# 06_interface.net
KiCad netlist of a schematic drawn in Altium Designer
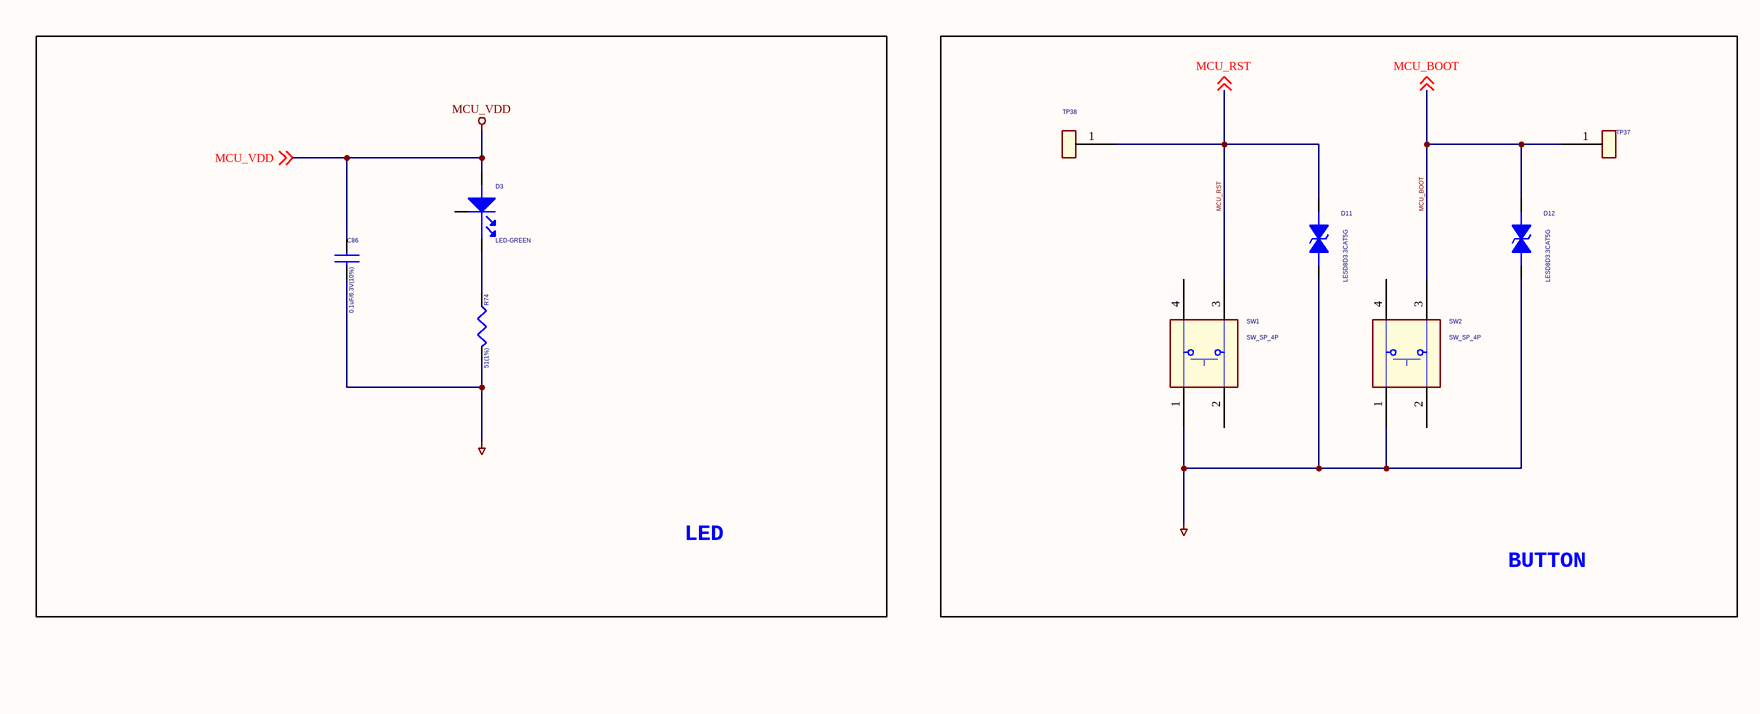
[diagram p0: 06_interface.SchDoc, left]
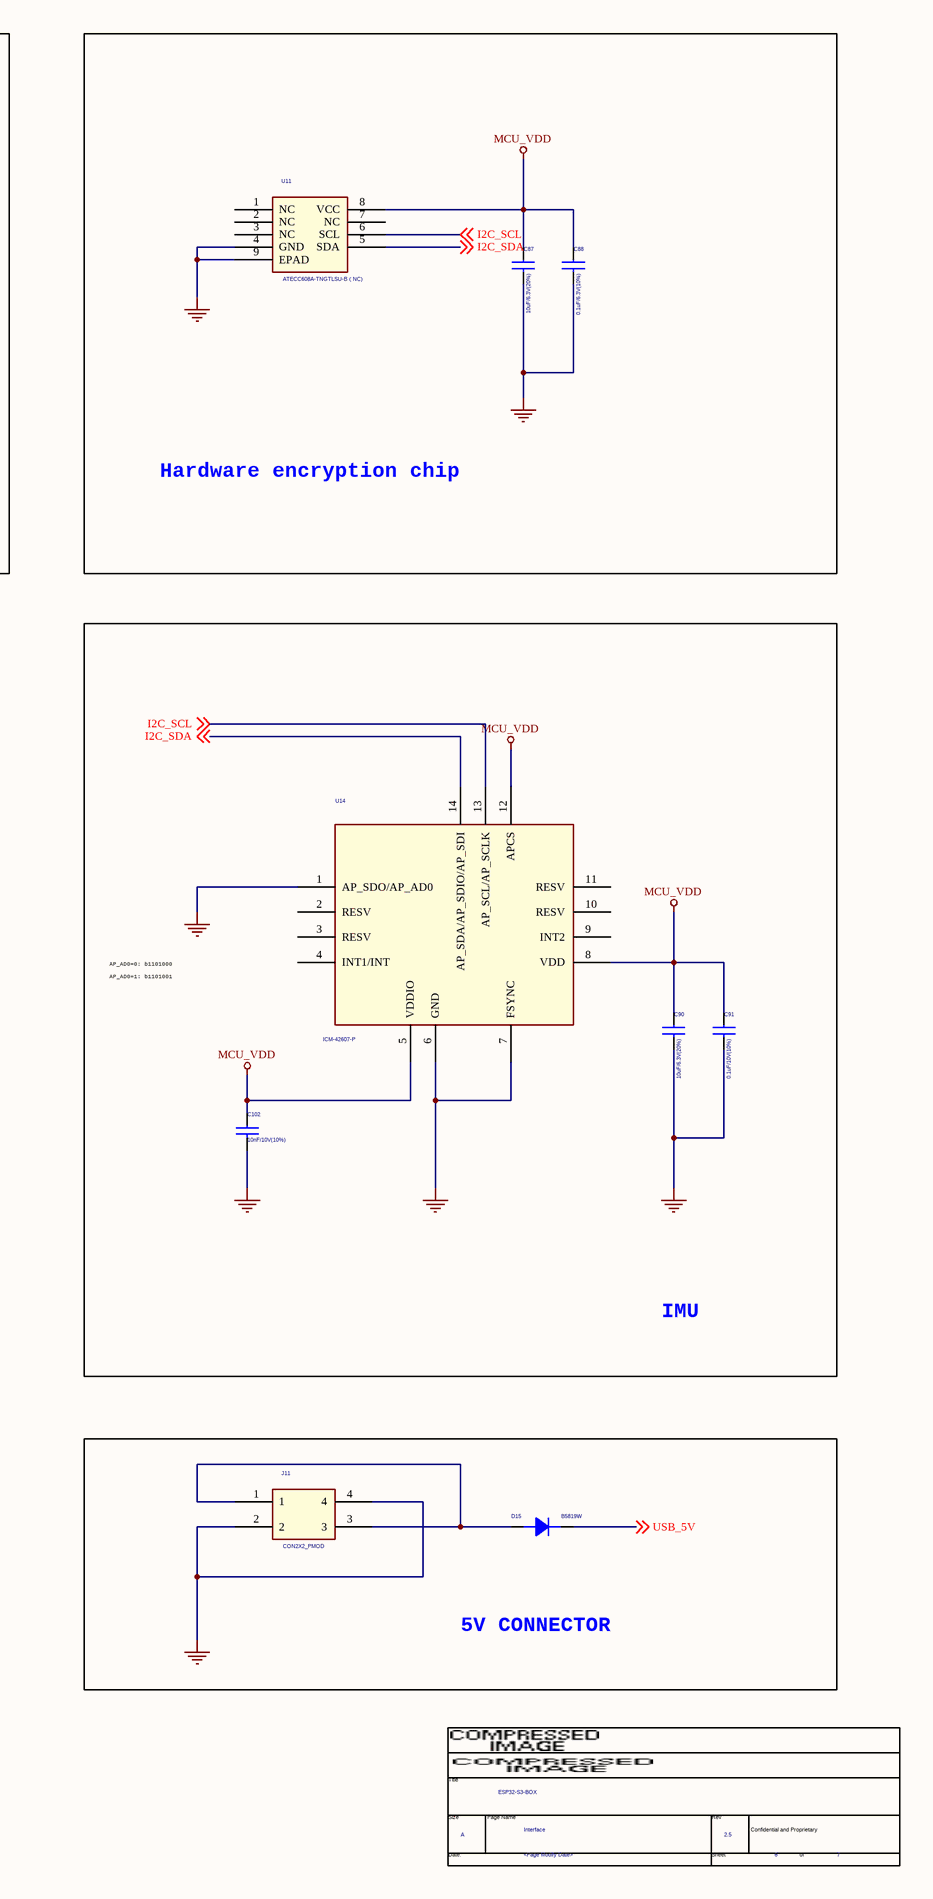
[diagram p1: 06_interface.SchDoc, right]

(export (version "E")
  (design (tool "Eeschema 10.0.6"))
  (components
    (comp (ref "*")
      (value "espTitleBlock3")
      (fields
        (field (name "PAGE MODIFY DATE") "<Page Modify Date>")
        (field (name "PAGE NAME") "Interface")
        (field (name "TITLE") "ESP32-S3-BOX")
        (field (name "PAGE SIZE") "A")
        (field (name "PAGE NUMBER") "6")
        (field (name "PAGE COUNT") "7")
        (field (name "REVCODE") "2.5")
      )
      (libsource (lib "*") (part "espTitleBlock3"))
    )
    (comp (ref "C86")
      (value "0.1uF/6.3V(10%)")
      (footprint "C0402")
      (fields (field (name "PART NUMBER") "ES11045102620001"))
      (libsource (lib "*") (part "CAPACITOR"))
    )
    (comp (ref "C87")
      (value "10uF/6.3V(20%)")
      (footprint "C0402")
      (fields (field (name "PART NUMBER") "ES11047102710000"))
      (libsource (lib "*") (part "CAPACITOR"))
    )
    (comp (ref "C88")
      (value "0.1uF/6.3V(10%)")
      (footprint "C0402")
      (fields (field (name "PART NUMBER") "ES11045102620001"))
      (libsource (lib "*") (part "CAPACITOR"))
    )
    (comp (ref "C90")
      (value "10uF/6.3V(20%)")
      (footprint "C0402")
      (fields (field (name "PART NUMBER") "ES11047102710000"))
      (libsource (lib "*") (part "CAPACITOR"))
    )
    (comp (ref "C91")
      (value "0.1uF/10V(10%)")
      (footprint "C0201")
      (fields (field (name "PART NUMBER") "ES11025103610001"))
      (libsource (lib "*") (part "CAPACITOR"))
    )
    (comp (ref "C102")
      (value "10nF/10V(10%)")
      (footprint "C0201")
      (fields (field (name "PART NUMBER") "ES11024103600000"))
      (libsource (lib "*") (part "CAPACITOR"))
    )
    (comp (ref "D3") (value "LED-GREEN") (footprint "LED_SMD1206") (libsource (lib "*") (part "LED-GREEN")))
    (comp (ref "D11")
      (value "LESD8D3.3CAT5G")
      (footprint "SOD882")
      (fields (field (name "PART NUMBER") "ES31320010000000"))
      (libsource (lib "*") (part "DIODE_BI_DIR"))
    )
    (comp (ref "D12")
      (value "LESD8D3.3CAT5G")
      (footprint "SOD882")
      (fields (field (name "PART NUMBER") "ES31320010000000"))
      (libsource (lib "*") (part "DIODE_BI_DIR"))
    )
    (comp (ref "D15")
      (value "B5819W")
      (footprint "SOD123")
      (fields (field (name "PART NUMBER") "ES31300150000000"))
      (libsource (lib "*") (part "DIODE_S"))
    )
    (comp (ref "J11")
      (value "CON2X2_PMOD")
      (footprint "CON2X2_PMOD")
      (libsource (lib "*") (part "CON2X2_PMOD"))
    )
    (comp (ref "R74")
      (value "51(1%)")
      (footprint "R0201")
      (fields (field (name "PART NUMBER") "ES21021510000001"))
      (libsource (lib "*") (part "RESISTOR"))
    )
    (comp (ref "SW1")
      (value "SW_SP_4P")
      (footprint "SW4-3X3P5X1P1-SMT")
      (libsource (lib "*") (part "SW_SP_4P"))
    )
    (comp (ref "SW2")
      (value "SW_SP_4P")
      (footprint "SW4-3X3P5X1P1-SMT")
      (libsource (lib "*") (part "SW_SP_4P"))
    )
    (comp (ref "TP37")
      (value "TESTPOINT")
      (footprint "TPC_D40")
      (fields (field (name "PART NUMBER") "ES51990010000000"))
      (libsource (lib "*") (part "TESTPOINT"))
    )
    (comp (ref "TP38")
      (value "TESTPOINT")
      (footprint "TPC_D40")
      (fields (field (name "PART NUMBER") "ES51990010000000"))
      (libsource (lib "") (part "TESTPOINT_1"))
    )
    (comp (ref "U11")
      (value "ATECC608A-TNGTLSU-B（NC)")
      (footprint "DFN8_0P5_2P4")
      (libsource (lib "*") (part "ATECC608A-TNGTLSU-B"))
    )
    (comp (ref "U14")
      (value "ICM-42607-P")
      (footprint "LGA14_0P5")
      (libsource (lib "*") (part "ICM-42607-P"))
    )
  )
  (nets
    (net (code "1") (name "GND") (class "Default")
      (node (ref "C102") (pin "2") (pinfunction "2_2") (pintype "passive"))
      (node (ref "C86") (pin "2") (pinfunction "2_2") (pintype "passive"))
      (node (ref "C87") (pin "2") (pinfunction "2_2") (pintype "passive"))
      (node (ref "C88") (pin "2") (pinfunction "2_2") (pintype "passive"))
      (node (ref "C90") (pin "2") (pinfunction "2_2") (pintype "passive"))
      (node (ref "C91") (pin "2") (pinfunction "2_2") (pintype "passive"))
      (node (ref "D11") (pin "1") (pinfunction "1_1") (pintype "passive"))
      (node (ref "D12") (pin "1") (pinfunction "1_1") (pintype "passive"))
      (node (ref "J11") (pin "2") (pinfunction "2_2") (pintype "passive"))
      (node (ref "J11") (pin "4") (pinfunction "4_4") (pintype "passive"))
      (node (ref "R74") (pin "2") (pinfunction "2_2") (pintype "passive"))
      (node (ref "SW1") (pin "1") (pinfunction "1_1") (pintype "passive"))
      (node (ref "SW2") (pin "1") (pinfunction "1_1") (pintype "passive"))
      (node (ref "U11") (pin "4") (pinfunction "GND_4") (pintype "passive"))
      (node (ref "U11") (pin "9") (pinfunction "EPAD_9") (pintype "passive"))
      (node (ref "U14") (pin "1") (pinfunction "AP_SDO/AP_AD0_1") (pintype "passive"))
      (node (ref "U14") (pin "6") (pinfunction "GND_6") (pintype "passive"))
      (node (ref "U14") (pin "7") (pinfunction "FSYNC_7") (pintype "passive"))
    )
    (net (code "2") (name "I2C_SCL") (class "Default")
      (node (ref "U11") (pin "6") (pinfunction "SCL_6") (pintype "passive"))
      (node (ref "U14") (pin "13") (pinfunction "AP_SCL/AP_SCLK_13") (pintype "passive"))
    )
    (net (code "3") (name "I2C_SDA") (class "Default")
      (node (ref "U11") (pin "5") (pinfunction "SDA_5") (pintype "passive"))
      (node (ref "U14") (pin "14") (pinfunction "AP_SDA/AP_SDIO/AP_SDI_14") (pintype "passive"))
    )
    (net (code "4") (name "MCU_BOOT") (class "Default")
      (node (ref "D12") (pin "2") (pinfunction "2_2") (pintype "passive"))
      (node (ref "SW2") (pin "3") (pinfunction "3_3") (pintype "passive"))
      (node (ref "TP37") (pin "1") (pinfunction "1_1") (pintype "passive"))
    )
    (net (code "5") (name "MCU_RST") (class "Default")
      (node (ref "D11") (pin "2") (pinfunction "2_2") (pintype "passive"))
      (node (ref "SW1") (pin "3") (pinfunction "3_3") (pintype "passive"))
      (node (ref "TP38") (pin "1") (pinfunction "1_1") (pintype "passive"))
    )
    (net (code "6") (name "MCU_VDD") (class "Default")
      (node (ref "C102") (pin "1") (pinfunction "1_1") (pintype "passive"))
      (node (ref "C86") (pin "1") (pinfunction "1_1") (pintype "passive"))
      (node (ref "C87") (pin "1") (pinfunction "1_1") (pintype "passive"))
      (node (ref "C88") (pin "1") (pinfunction "1_1") (pintype "passive"))
      (node (ref "C90") (pin "1") (pinfunction "1_1") (pintype "passive"))
      (node (ref "C91") (pin "1") (pinfunction "1_1") (pintype "passive"))
      (node (ref "D3") (pin "1") (pinfunction "1_1") (pintype "passive"))
      (node (ref "U11") (pin "8") (pinfunction "VCC_8") (pintype "passive"))
      (node (ref "U14") (pin "12") (pinfunction "APCS_12") (pintype "passive"))
      (node (ref "U14") (pin "5") (pinfunction "VDDIO_5") (pintype "passive"))
      (node (ref "U14") (pin "8") (pinfunction "VDD_8") (pintype "passive"))
    )
    (net (code "7") (name "Net-(D3-Pad2)") (class "Default")
      (node (ref "D3") (pin "2") (pinfunction "2_2") (pintype "passive"))
      (node (ref "R74") (pin "1") (pinfunction "1_1") (pintype "passive"))
    )
    (net (code "8") (name "Net-(D15-A)") (class "Default")
      (node (ref "D15") (pin "1") (pinfunction "A_1") (pintype "passive"))
      (node (ref "J11") (pin "1") (pinfunction "1_1") (pintype "passive"))
      (node (ref "J11") (pin "3") (pinfunction "3_3") (pintype "passive"))
    )
    (net (code "9") (name "USB_5V") (class "Default")
      (node (ref "D15") (pin "2") (pinfunction "K_2") (pintype "passive"))
    )
    (net (code "10") (name "unconnected-(D3-Pad3)") (class "Default")
      (node (ref "D3") (pin "3") (pinfunction "3_3") (pintype "passive"))
    )
    (net (code "11") (name "unconnected-(SW1-Pad2)") (class "Default")
      (node (ref "SW1") (pin "2") (pinfunction "2_2") (pintype "passive"))
    )
    (net (code "12") (name "unconnected-(SW1-Pad4)") (class "Default")
      (node (ref "SW1") (pin "4") (pinfunction "4_4") (pintype "passive"))
    )
    (net (code "13") (name "unconnected-(SW2-Pad2)") (class "Default")
      (node (ref "SW2") (pin "2") (pinfunction "2_2") (pintype "passive"))
    )
    (net (code "14") (name "unconnected-(SW2-Pad4)") (class "Default")
      (node (ref "SW2") (pin "4") (pinfunction "4_4") (pintype "passive"))
    )
    (net (code "15") (name "unconnected-(U11-NC-Pad1)") (class "Default")
      (node (ref "U11") (pin "1") (pinfunction "NC_1") (pintype "passive"))
    )
    (net (code "16") (name "unconnected-(U11-NC-Pad2)") (class "Default")
      (node (ref "U11") (pin "2") (pinfunction "NC_2") (pintype "passive"))
    )
    (net (code "17") (name "unconnected-(U11-NC-Pad3)") (class "Default")
      (node (ref "U11") (pin "3") (pinfunction "NC_3") (pintype "passive"))
    )
    (net (code "18") (name "unconnected-(U11-NC-Pad7)") (class "Default")
      (node (ref "U11") (pin "7") (pinfunction "NC_7") (pintype "passive"))
    )
    (net (code "19") (name "unconnected-(U14-INT1{slash}INT-Pad4)") (class "Default")
      (node (ref "U14") (pin "4") (pinfunction "INT1/INT_4") (pintype "passive"))
    )
    (net (code "20") (name "unconnected-(U14-INT2-Pad9)") (class "Default")
      (node (ref "U14") (pin "9") (pinfunction "INT2_9") (pintype "passive"))
    )
    (net (code "21") (name "unconnected-(U14-RESV-Pad2)") (class "Default")
      (node (ref "U14") (pin "2") (pinfunction "RESV_2") (pintype "passive"))
    )
    (net (code "22") (name "unconnected-(U14-RESV-Pad3)") (class "Default")
      (node (ref "U14") (pin "3") (pinfunction "RESV_3") (pintype "passive"))
    )
    (net (code "23") (name "unconnected-(U14-RESV-Pad10)") (class "Default")
      (node (ref "U14") (pin "10") (pinfunction "RESV_10") (pintype "passive"))
    )
    (net (code "24") (name "unconnected-(U14-RESV-Pad11)") (class "Default")
      (node (ref "U14") (pin "11") (pinfunction "RESV_11") (pintype "passive"))
    )
  )
)
